# andEight_mouv4k.net
KiCad netlist of a schematic drawn in EAGLE
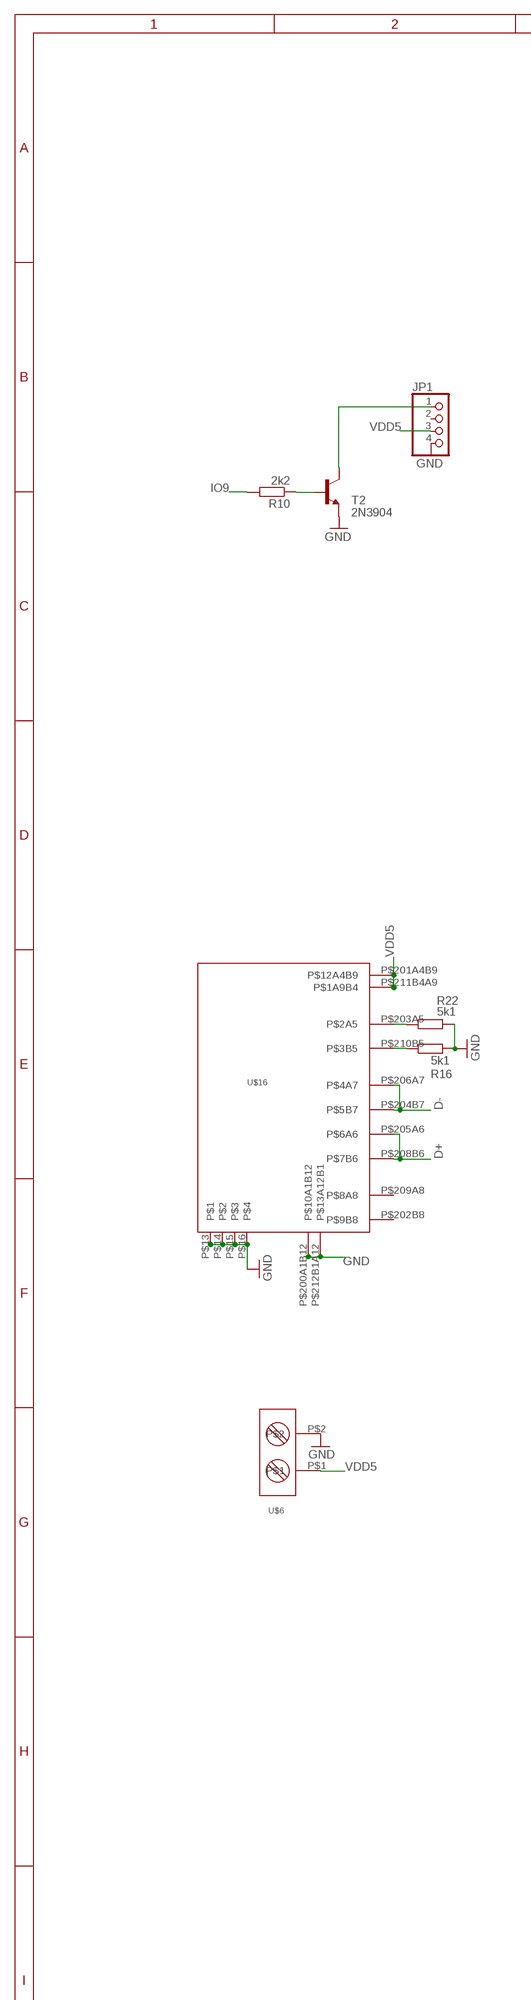
[diagram p0: schematic, sheet 1, part 1 of 2]
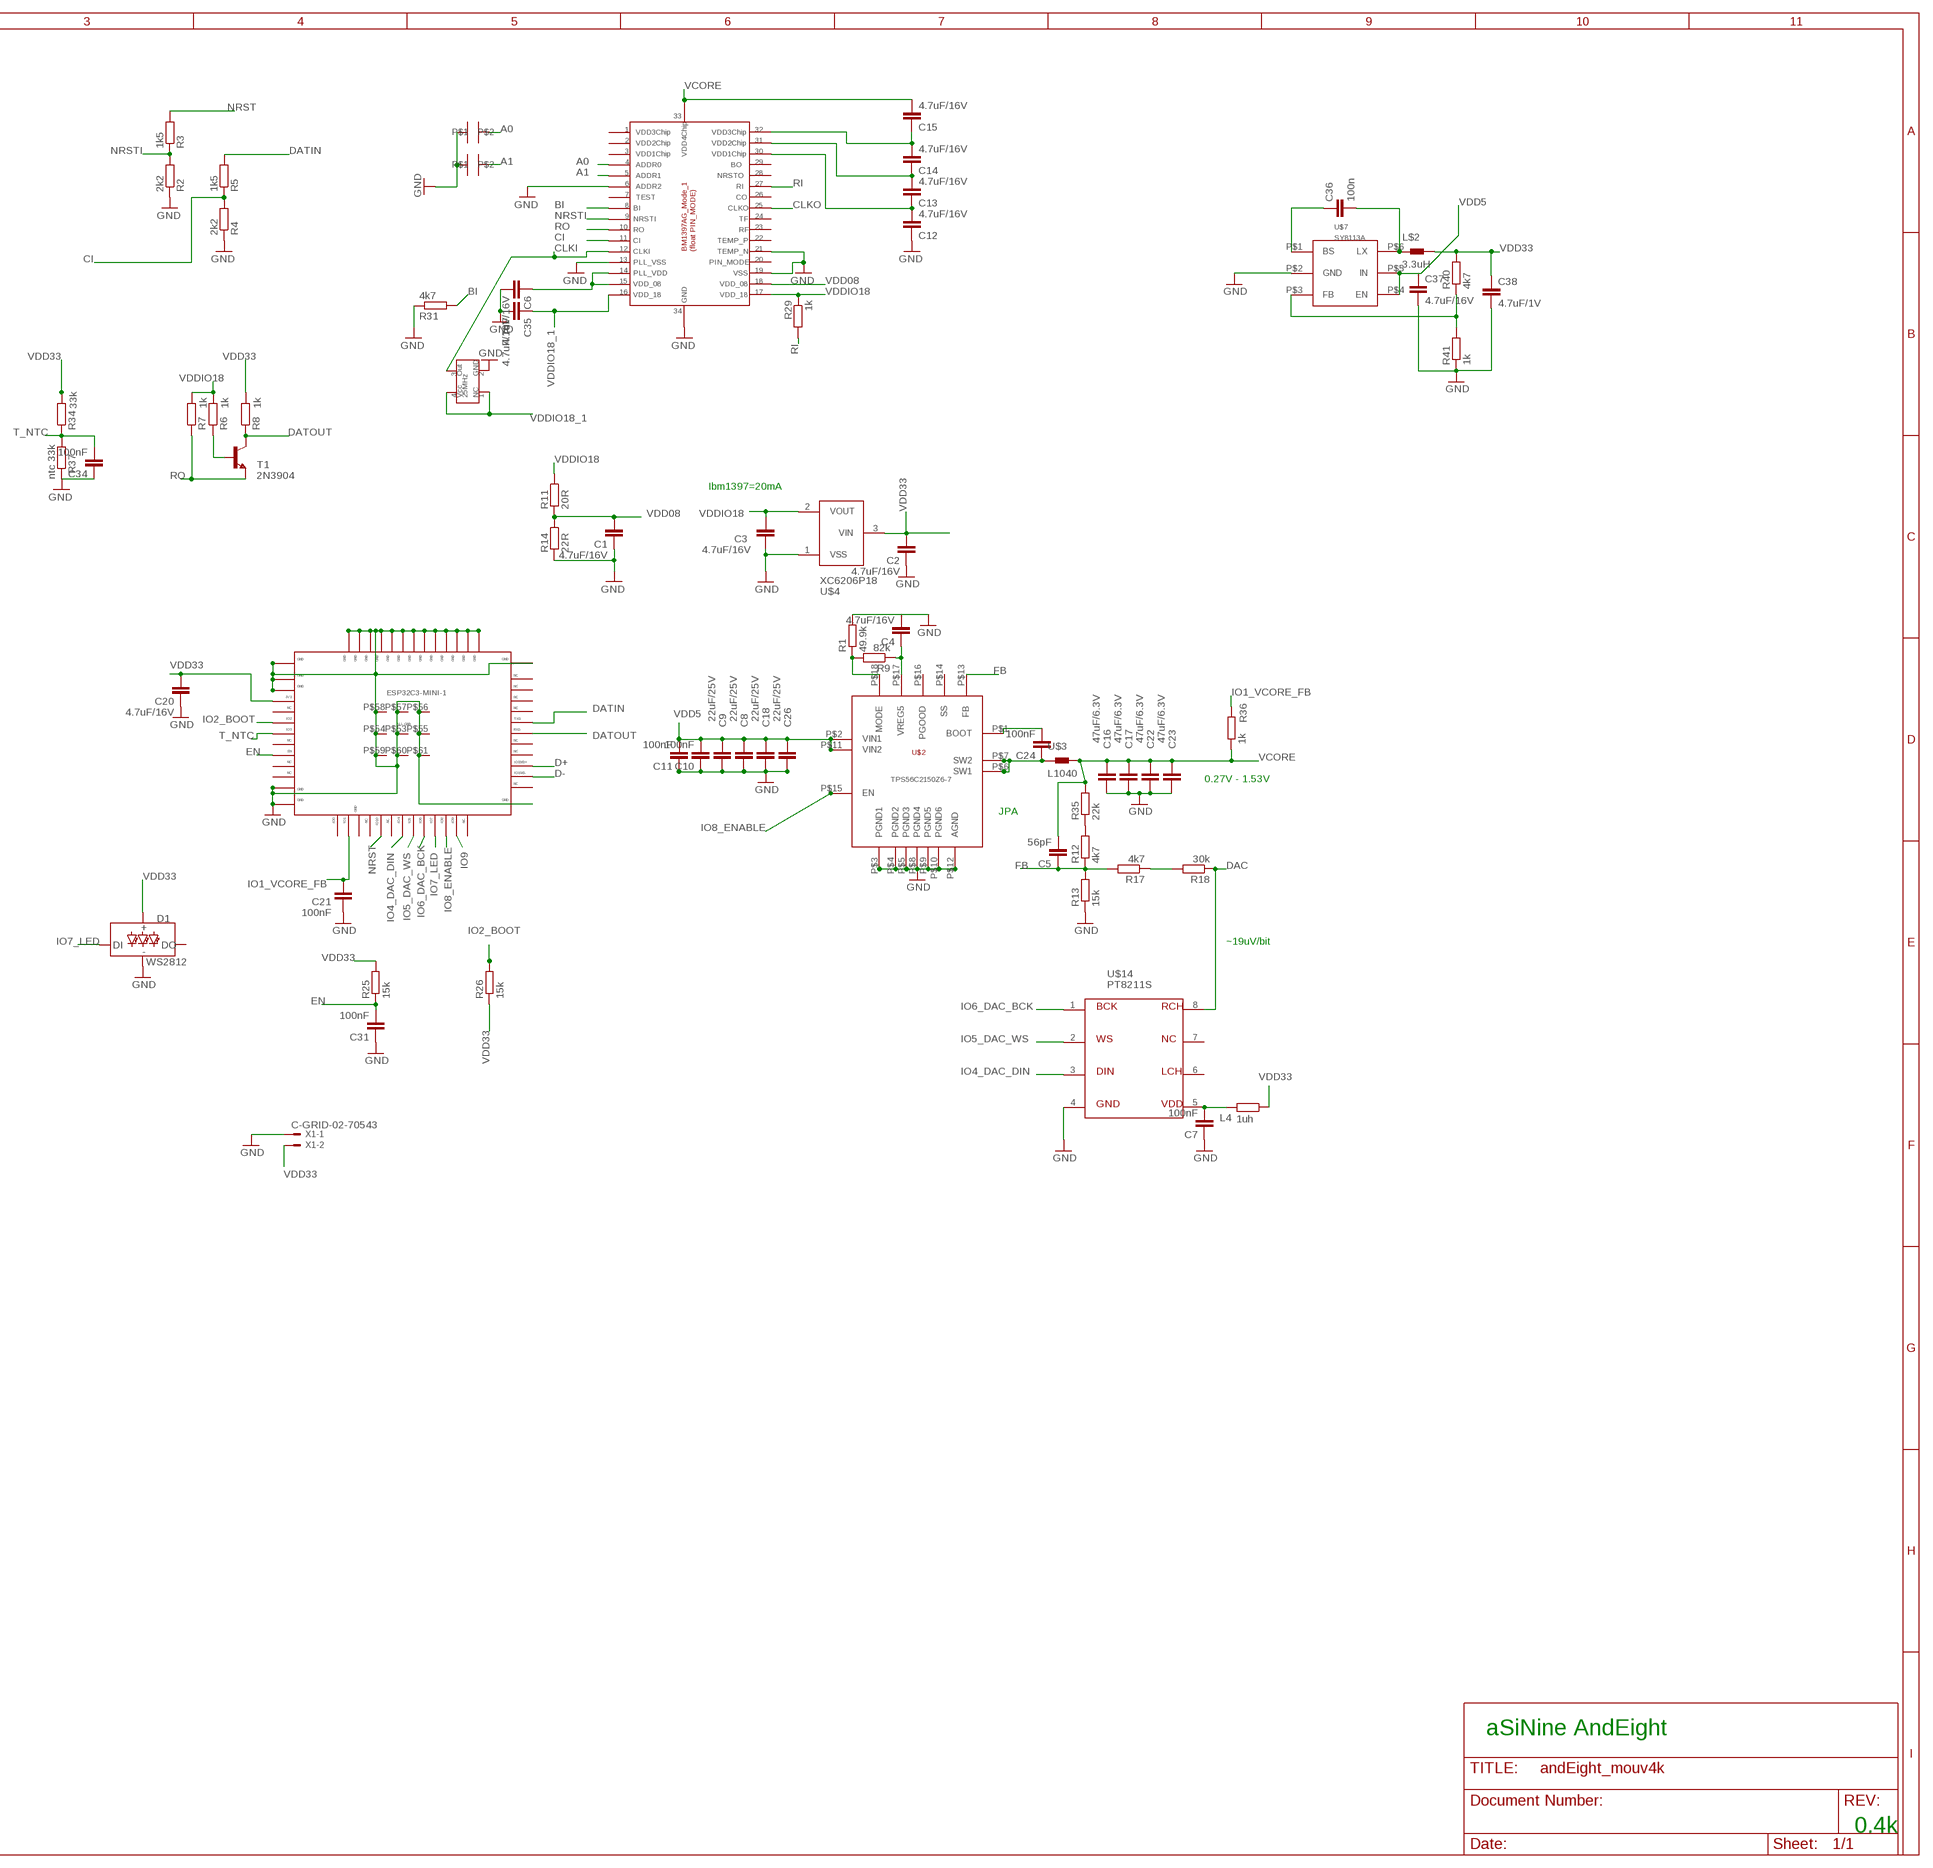
[diagram p1: schematic, sheet 1, part 2 of 2]

(export (version "E")
  (design (tool "Eeschema 10.0.6"))
  (components
    (comp (ref "A0")
      (value "SOLDERJUMPER")
      (footprint "eagle-import:SOLDERJUMPER")
      (libsource (lib "eagle-import") (part "SOLDERJUMPER"))
    )
    (comp (ref "A1")
      (value "SOLDERJUMPER")
      (footprint "eagle-import:SOLDERJUMPER")
      (libsource (lib "eagle-import") (part "SOLDERJUMPER"))
    )
    (comp (ref "C1")
      (value "4.7uF/16V")
      (footprint "eagle-import:C0402")
      (libsource (lib "eagle-import") (part "C-EUC0402"))
    )
    (comp (ref "C2")
      (value "4.7uF/16V")
      (footprint "eagle-import:C0402")
      (libsource (lib "eagle-import") (part "C-EUC0402"))
    )
    (comp (ref "C3")
      (value "4.7uF/16V")
      (footprint "eagle-import:C0402")
      (libsource (lib "eagle-import") (part "C-EUC0402"))
    )
    (comp (ref "C4")
      (value "4.7uF/16V")
      (footprint "eagle-import:C0402")
      (libsource (lib "eagle-import") (part "C-EUC0402"))
    )
    (comp (ref "C5")
      (value "56pF")
      (footprint "eagle-import:C0402")
      (libsource (lib "eagle-import") (part "C-EUC0402"))
    )
    (comp (ref "C6")
      (value "4.7uF/16V")
      (footprint "eagle-import:C0402")
      (libsource (lib "eagle-import") (part "C-EUC0402"))
    )
    (comp (ref "C7")
      (value "100nF")
      (footprint "eagle-import:C0402")
      (libsource (lib "eagle-import") (part "C-EUC0402"))
    )
    (comp (ref "C8")
      (value "22uF/25V")
      (footprint "eagle-import:C0805")
      (libsource (lib "eagle-import") (part "C-EUC0805"))
    )
    (comp (ref "C9")
      (value "22uF/25V")
      (footprint "eagle-import:C0805")
      (libsource (lib "eagle-import") (part "C-EUC0805"))
    )
    (comp (ref "C10")
      (value "100nF")
      (footprint "eagle-import:C0402")
      (libsource (lib "eagle-import") (part "C-EUC0402"))
    )
    (comp (ref "C11")
      (value "100nF")
      (footprint "eagle-import:C0402")
      (libsource (lib "eagle-import") (part "C-EUC0402"))
    )
    (comp (ref "C12")
      (value "4.7uF/16V")
      (footprint "eagle-import:C0402")
      (libsource (lib "eagle-import") (part "C-EUC0402"))
    )
    (comp (ref "C13")
      (value "4.7uF/16V")
      (footprint "eagle-import:C0402")
      (libsource (lib "eagle-import") (part "C-EUC0402"))
    )
    (comp (ref "C14")
      (value "4.7uF/16V")
      (footprint "eagle-import:C0402")
      (libsource (lib "eagle-import") (part "C-EUC0402"))
    )
    (comp (ref "C15")
      (value "4.7uF/16V")
      (footprint "eagle-import:C0402")
      (libsource (lib "eagle-import") (part "C-EUC0402"))
    )
    (comp (ref "C16")
      (value "47uF/6.3V")
      (footprint "eagle-import:C0805")
      (libsource (lib "eagle-import") (part "C-EUC0805"))
    )
    (comp (ref "C17")
      (value "47uF/6.3V")
      (footprint "eagle-import:C0805")
      (libsource (lib "eagle-import") (part "C-EUC0805"))
    )
    (comp (ref "C18")
      (value "22uF/25V")
      (footprint "eagle-import:C0805")
      (libsource (lib "eagle-import") (part "C-EUC0805"))
    )
    (comp (ref "C20")
      (value "4.7uF/16V")
      (footprint "eagle-import:C0603")
      (libsource (lib "eagle-import") (part "C-EUC0603"))
    )
    (comp (ref "C21")
      (value "100nF")
      (footprint "eagle-import:C0603")
      (libsource (lib "eagle-import") (part "C-EUC0603"))
    )
    (comp (ref "C22")
      (value "47uF/6.3V")
      (footprint "eagle-import:C0805")
      (libsource (lib "eagle-import") (part "C-EUC0805"))
    )
    (comp (ref "C23")
      (value "47uF/6.3V")
      (footprint "eagle-import:C0805")
      (libsource (lib "eagle-import") (part "C-EUC0805"))
    )
    (comp (ref "C24")
      (value "100nF")
      (footprint "eagle-import:C0402")
      (libsource (lib "eagle-import") (part "C-EUC0402"))
    )
    (comp (ref "C26")
      (value "22uF/25V")
      (footprint "eagle-import:C0805")
      (libsource (lib "eagle-import") (part "C-EUC0805"))
    )
    (comp (ref "C31")
      (value "100nF")
      (footprint "eagle-import:C0402")
      (libsource (lib "eagle-import") (part "C-EUC0402"))
    )
    (comp (ref "C34")
      (value "100nF")
      (footprint "eagle-import:C0402")
      (libsource (lib "eagle-import") (part "C-EUC0402"))
    )
    (comp (ref "C35")
      (value "4.7uF/16V")
      (footprint "eagle-import:C0402")
      (libsource (lib "eagle-import") (part "C-EUC0402"))
    )
    (comp (ref "C36")
      (value "100n")
      (footprint "eagle-import:C0402")
      (libsource (lib "eagle-import") (part "C-EUC0402"))
    )
    (comp (ref "C37")
      (value "4.7uF/16V")
      (footprint "eagle-import:C0402")
      (libsource (lib "eagle-import") (part "C-EUC0402"))
    )
    (comp (ref "C38")
      (value "4.7uF/1V")
      (footprint "eagle-import:C0402")
      (libsource (lib "eagle-import") (part "C-EUC0402"))
    )
    (comp (ref "D1")
      (value "WS2812")
      (footprint "eagle-import:WS2812-5X5-4PIN")
      (libsource (lib "eagle-import") (part "WS2812_5050"))
    )
    (comp (ref "ESP32C3-MINI-1")
      (value "ESP32-C3-MINI-1")
      (footprint "eagle-import:ESP32C3MINI")
      (libsource (lib "eagle-import") (part "ESP32C3MINI"))
    )
    (comp (ref "JP1")
      (value "PINHD-1X4/90")
      (footprint "eagle-import:1X04_90")
      (libsource (lib "eagle-import") (part "PINHD-1X4/90"))
    )
    (comp (ref "L$2")
      (value "3.3uH")
      (footprint "eagle-import:NR201610")
      (libsource (lib "eagle-import") (part "NR201610"))
    )
    (comp (ref "L4")
      (value "1uh")
      (footprint "eagle-import:R0402")
      (libsource (lib "eagle-import") (part "R-EU_R0402"))
    )
    (comp (ref "R1")
      (value "49.9k")
      (footprint "eagle-import:R0402")
      (libsource (lib "eagle-import") (part "R-EU_R0402"))
    )
    (comp (ref "R2")
      (value "2k2")
      (footprint "eagle-import:R0402")
      (libsource (lib "eagle-import") (part "R-EU_R0402"))
    )
    (comp (ref "R3")
      (value "1k5")
      (footprint "eagle-import:R0402")
      (libsource (lib "eagle-import") (part "R-EU_R0402"))
    )
    (comp (ref "R4")
      (value "2k2")
      (footprint "eagle-import:R0402")
      (libsource (lib "eagle-import") (part "R-EU_R0402"))
    )
    (comp (ref "R5")
      (value "1k5")
      (footprint "eagle-import:R0402")
      (libsource (lib "eagle-import") (part "R-EU_R0402"))
    )
    (comp (ref "R6")
      (value "1k")
      (footprint "eagle-import:R0402")
      (libsource (lib "eagle-import") (part "R-EU_R0402"))
    )
    (comp (ref "R7")
      (value "1k")
      (footprint "eagle-import:R0402")
      (libsource (lib "eagle-import") (part "R-EU_R0402"))
    )
    (comp (ref "R8")
      (value "1k")
      (footprint "eagle-import:R0402")
      (libsource (lib "eagle-import") (part "R-EU_R0402"))
    )
    (comp (ref "R9")
      (value "82k")
      (footprint "eagle-import:R0402")
      (libsource (lib "eagle-import") (part "R-EU_R0402"))
    )
    (comp (ref "R10")
      (value "2k2")
      (footprint "eagle-import:R0402")
      (libsource (lib "eagle-import") (part "R-EU_R0402"))
    )
    (comp (ref "R11")
      (value "20R")
      (footprint "eagle-import:R0402")
      (libsource (lib "eagle-import") (part "R-EU_R0402"))
    )
    (comp (ref "R12")
      (value "4k7")
      (footprint "eagle-import:R0402")
      (libsource (lib "eagle-import") (part "R-EU_R0402"))
    )
    (comp (ref "R13")
      (value "15k")
      (footprint "eagle-import:R0402")
      (libsource (lib "eagle-import") (part "R-EU_R0402"))
    )
    (comp (ref "R14")
      (value "22R")
      (footprint "eagle-import:R0402")
      (libsource (lib "eagle-import") (part "R-EU_R0402"))
    )
    (comp (ref "R16")
      (value "5k1")
      (footprint "eagle-import:R0402")
      (libsource (lib "eagle-import") (part "R-EU_R0402"))
    )
    (comp (ref "R17")
      (value "4k7")
      (footprint "eagle-import:R0402")
      (libsource (lib "eagle-import") (part "R-EU_R0402"))
    )
    (comp (ref "R18")
      (value "30k")
      (footprint "eagle-import:R0402")
      (libsource (lib "eagle-import") (part "R-EU_R0402"))
    )
    (comp (ref "R22")
      (value "5k1")
      (footprint "eagle-import:R0402")
      (libsource (lib "eagle-import") (part "R-EU_R0402"))
    )
    (comp (ref "R25")
      (value "15k")
      (footprint "eagle-import:R0402")
      (libsource (lib "eagle-import") (part "R-EU_R0402"))
    )
    (comp (ref "R26")
      (value "15k")
      (footprint "eagle-import:R0402")
      (libsource (lib "eagle-import") (part "R-EU_R0402"))
    )
    (comp (ref "R29")
      (value "1k")
      (footprint "eagle-import:R0402")
      (libsource (lib "eagle-import") (part "R-EU_R0402"))
    )
    (comp (ref "R31")
      (value "4k7")
      (footprint "eagle-import:R0402")
      (libsource (lib "eagle-import") (part "R-EU_R0402"))
    )
    (comp (ref "R34")
      (value "33k")
      (footprint "eagle-import:R0603")
      (libsource (lib "eagle-import") (part "R-EU_R0603"))
    )
    (comp (ref "R35")
      (value "22k")
      (footprint "eagle-import:R0402")
      (libsource (lib "eagle-import") (part "R-EU_R0402"))
    )
    (comp (ref "R36")
      (value "1k")
      (footprint "eagle-import:R0402")
      (libsource (lib "eagle-import") (part "R-EU_R0402"))
    )
    (comp (ref "R37")
      (value "ntc 33k")
      (footprint "eagle-import:R0402")
      (libsource (lib "eagle-import") (part "R-EU_R0402"))
    )
    (comp (ref "R40")
      (value "4k7")
      (footprint "eagle-import:R0402")
      (libsource (lib "eagle-import") (part "R-EU_R0402"))
    )
    (comp (ref "R41")
      (value "1k")
      (footprint "eagle-import:R0402")
      (libsource (lib "eagle-import") (part "R-EU_R0402"))
    )
    (comp (ref "T1")
      (value "2N3904")
      (footprint "eagle-import:SOT23")
      (libsource (lib "eagle-import") (part "BC847"))
    )
    (comp (ref "T2")
      (value "2N3904")
      (footprint "eagle-import:SOT23")
      (libsource (lib "eagle-import") (part "BC847"))
    )
    (comp (ref "U$1")
      (value "BM1397-1")
      (footprint "eagle-import:BM1391")
      (libsource (lib "eagle-import") (part "BM1397-1"))
    )
    (comp (ref "U$2")
      (value "TPS56C2150Z6-7")
      (footprint "eagle-import:VQFN-HR")
      (libsource (lib "eagle-import") (part "TPS56C2150Z6-7"))
    )
    (comp (ref "U$3")
      (value "L1040")
      (footprint "eagle-import:L1040")
      (libsource (lib "eagle-import") (part "L1040"))
    )
    (comp (ref "U$4")
      (value "XC6206P18")
      (footprint "eagle-import:SOT23")
      (libsource (lib "eagle-import") (part "XC6206P"))
    )
    (comp (ref "U$6")
      (value "DG301-50")
      (footprint "eagle-import:DG301-50")
      (libsource (lib "eagle-import") (part "DG301-50"))
    )
    (comp (ref "U$7")
      (value "SY8113A")
      (footprint "eagle-import:SOT23L-6")
      (libsource (lib "eagle-import") (part "SY8113A"))
    )
    (comp (ref "U$14")
      (value "PT8211S")
      (footprint "eagle-import:SO-8")
      (libsource (lib "eagle-import") (part "PT8211"))
    )
    (comp (ref "U$16")
      (value "USBCTHT")
      (footprint "eagle-import:USBCSMTTHT")
      (libsource (lib "eagle-import") (part "USBCTHT"))
    )
    (comp (ref "U$22")
      (value "25MHz")
      (footprint "eagle-import:3225")
      (libsource (lib "eagle-import") (part "OSC3225"))
    )
    (comp (ref "X1")
      (value "C-GRID-02-70543")
      (footprint "eagle-import:70543-02")
      (libsource (lib "eagle-import") (part "C-GRID-02-70543"))
    )
  )
  (nets
    (net (code "1") (name "/A0") (class "Default")
      (node (ref "A0") (pin "P$1") (pinfunction "P$1_P$1") (pintype "bidirectional"))
      (node (ref "U$1") (pin "P$4") (pinfunction "P$4_P$4") (pintype "bidirectional"))
    )
    (net (code "2") (name "/A1") (class "Default")
      (node (ref "A1") (pin "P$1") (pinfunction "P$1_P$1") (pintype "bidirectional"))
      (node (ref "U$1") (pin "P$5") (pinfunction "P$5_P$5") (pintype "bidirectional"))
    )
    (net (code "3") (name "/BI") (class "Default")
      (node (ref "R31") (pin "2") (pinfunction "2_2") (pintype "passive"))
      (node (ref "U$1") (pin "P$8") (pinfunction "P$8_P$8") (pintype "bidirectional"))
    )
    (net (code "4") (name "/CI") (class "Default")
      (node (ref "R4") (pin "2") (pinfunction "2_2") (pintype "passive"))
      (node (ref "R5") (pin "1") (pinfunction "1_1") (pintype "passive"))
      (node (ref "U$1") (pin "P$11") (pinfunction "P$11_P$11") (pintype "bidirectional"))
    )
    (net (code "5") (name "/CLKI") (class "Default")
      (node (ref "U$1") (pin "P$12") (pinfunction "P$12_P$12") (pintype "bidirectional"))
      (node (ref "U$22") (pin "P$3") (pinfunction "P$3_P$3") (pintype "bidirectional"))
    )
    (net (code "6") (name "/CLKO") (class "Default")
      (node (ref "U$1") (pin "P$25") (pinfunction "P$25_P$25") (pintype "bidirectional"))
    )
    (net (code "7") (name "/D+") (class "Default")
      (node (ref "ESP32C3-MINI-1") (pin "P$27") (pinfunction "P$27_P$27") (pintype "bidirectional"))
      (node (ref "U$16") (pin "P$205A6") (pinfunction "P$6A6_P$205A6") (pintype "bidirectional"))
      (node (ref "U$16") (pin "P$208B6") (pinfunction "P$7B6_P$208B6") (pintype "bidirectional"))
    )
    (net (code "8") (name "/D-") (class "Default")
      (node (ref "ESP32C3-MINI-1") (pin "P$26") (pinfunction "P$26_P$26") (pintype "bidirectional"))
      (node (ref "U$16") (pin "P$204B7") (pinfunction "P$5B7_P$204B7") (pintype "bidirectional"))
      (node (ref "U$16") (pin "P$206A7") (pinfunction "P$4A7_P$206A7") (pintype "bidirectional"))
    )
    (net (code "9") (name "/DAC") (class "Default")
      (node (ref "R18") (pin "1") (pinfunction "1_1") (pintype "passive"))
      (node (ref "U$14") (pin "8") (pinfunction "P$8_8") (pintype "bidirectional"))
    )
    (net (code "10") (name "/DATIN") (class "Default")
      (node (ref "ESP32C3-MINI-1") (pin "P$31") (pinfunction "P$31_P$31") (pintype "bidirectional"))
      (node (ref "R5") (pin "2") (pinfunction "2_2") (pintype "passive"))
    )
    (net (code "11") (name "/DATOUT") (class "Default")
      (node (ref "ESP32C3-MINI-1") (pin "P$30") (pinfunction "P$30_P$30") (pintype "bidirectional"))
      (node (ref "R8") (pin "1") (pinfunction "1_1") (pintype "passive"))
      (node (ref "T1") (pin "3") (pinfunction "C_3") (pintype "passive"))
    )
    (net (code "12") (name "/EN") (class "Default")
      (node (ref "C31") (pin "2") (pinfunction "2_2") (pintype "passive"))
      (node (ref "ESP32C3-MINI-1") (pin "P$8") (pinfunction "P$8_P$8") (pintype "bidirectional"))
      (node (ref "R25") (pin "1") (pinfunction "1_1") (pintype "passive"))
    )
    (net (code "13") (name "/FB") (class "Default")
      (node (ref "C5") (pin "1") (pinfunction "1_1") (pintype "passive"))
      (node (ref "R12") (pin "1") (pinfunction "1_1") (pintype "passive"))
      (node (ref "R13") (pin "2") (pinfunction "2_2") (pintype "passive"))
      (node (ref "R17") (pin "2") (pinfunction "2_2") (pintype "passive"))
      (node (ref "U$2") (pin "P$13") (pinfunction "FB_P$13") (pintype "bidirectional"))
    )
    (net (code "14") (name "/IO1_VCORE_FB") (class "Default")
      (node (ref "C21") (pin "2") (pinfunction "2_2") (pintype "passive"))
      (node (ref "ESP32C3-MINI-1") (pin "P$13") (pinfunction "P$13_P$13") (pintype "bidirectional"))
      (node (ref "R36") (pin "2") (pinfunction "2_2") (pintype "passive"))
    )
    (net (code "15") (name "/IO2_BOOT") (class "Default")
      (node (ref "ESP32C3-MINI-1") (pin "P$5") (pinfunction "P$5_P$5") (pintype "bidirectional"))
      (node (ref "R26") (pin "2") (pinfunction "2_2") (pintype "passive"))
    )
    (net (code "16") (name "/IO4_DAC_DIN") (class "Default")
      (node (ref "ESP32C3-MINI-1") (pin "P$18") (pinfunction "P$18_P$18") (pintype "bidirectional"))
      (node (ref "U$14") (pin "3") (pinfunction "P$3_3") (pintype "bidirectional"))
    )
    (net (code "17") (name "/IO5_DAC_WS") (class "Default")
      (node (ref "ESP32C3-MINI-1") (pin "P$19") (pinfunction "P$19_P$19") (pintype "bidirectional"))
      (node (ref "U$14") (pin "2") (pinfunction "P$2_2") (pintype "bidirectional"))
    )
    (net (code "18") (name "/IO6_DAC_BCK") (class "Default")
      (node (ref "ESP32C3-MINI-1") (pin "P$20") (pinfunction "P$20_P$20") (pintype "bidirectional"))
      (node (ref "U$14") (pin "1") (pinfunction "P$1_1") (pintype "bidirectional"))
    )
    (net (code "19") (name "/IO7_LED") (class "Default")
      (node (ref "D1") (pin "DI") (pinfunction "DI_DI") (pintype "bidirectional"))
      (node (ref "ESP32C3-MINI-1") (pin "P$21") (pinfunction "P$21_P$21") (pintype "bidirectional"))
    )
    (net (code "20") (name "/IO8_ENABLE") (class "Default")
      (node (ref "ESP32C3-MINI-1") (pin "P$22") (pinfunction "P$22_P$22") (pintype "bidirectional"))
      (node (ref "U$2") (pin "P$15") (pinfunction "EN_P$15") (pintype "bidirectional"))
    )
    (net (code "21") (name "/IO9") (class "Default")
      (node (ref "ESP32C3-MINI-1") (pin "P$23") (pinfunction "P$23_P$23") (pintype "bidirectional"))
      (node (ref "R10") (pin "2") (pinfunction "2_2") (pintype "passive"))
    )
    (net (code "22") (name "/NRST") (class "Default")
      (node (ref "ESP32C3-MINI-1") (pin "P$16") (pinfunction "P$16_P$16") (pintype "bidirectional"))
      (node (ref "R3") (pin "2") (pinfunction "2_2") (pintype "passive"))
    )
    (net (code "23") (name "/NRSTI") (class "Default")
      (node (ref "R2") (pin "2") (pinfunction "2_2") (pintype "passive"))
      (node (ref "R3") (pin "1") (pinfunction "1_1") (pintype "passive"))
      (node (ref "U$1") (pin "P$9") (pinfunction "P$9_P$9") (pintype "bidirectional"))
    )
    (net (code "24") (name "/RI") (class "Default")
      (node (ref "R29") (pin "2") (pinfunction "2_2") (pintype "passive"))
      (node (ref "U$1") (pin "P$27") (pinfunction "P$27_P$27") (pintype "bidirectional"))
    )
    (net (code "25") (name "/RO") (class "Default")
      (node (ref "R7") (pin "1") (pinfunction "1_1") (pintype "passive"))
      (node (ref "T1") (pin "2") (pinfunction "E_2") (pintype "passive"))
      (node (ref "U$1") (pin "P$10") (pinfunction "P$10_P$10") (pintype "bidirectional"))
    )
    (net (code "26") (name "/T_NTC") (class "Default")
      (node (ref "C34") (pin "2") (pinfunction "2_2") (pintype "passive"))
      (node (ref "ESP32C3-MINI-1") (pin "P$6") (pinfunction "P$6_P$6") (pintype "bidirectional"))
      (node (ref "R34") (pin "1") (pinfunction "1_1") (pintype "passive"))
      (node (ref "R37") (pin "2") (pinfunction "2_2") (pintype "passive"))
    )
    (net (code "27") (name "/VCORE") (class "Default")
      (node (ref "C15") (pin "2") (pinfunction "2_2") (pintype "passive"))
      (node (ref "C16") (pin "1") (pinfunction "1_1") (pintype "passive"))
      (node (ref "C17") (pin "1") (pinfunction "1_1") (pintype "passive"))
      (node (ref "C22") (pin "1") (pinfunction "1_1") (pintype "passive"))
      (node (ref "C23") (pin "1") (pinfunction "1_1") (pintype "passive"))
      (node (ref "C5") (pin "2") (pinfunction "2_2") (pintype "passive"))
      (node (ref "R35") (pin "2") (pinfunction "2_2") (pintype "passive"))
      (node (ref "R36") (pin "1") (pinfunction "1_1") (pintype "passive"))
      (node (ref "U$1") (pin "P$33") (pinfunction "P$33_P$33") (pintype "bidirectional"))
      (node (ref "U$3") (pin "P$2") (pinfunction "2_P$2") (pintype "passive"))
    )
    (net (code "28") (name "/VDD5") (class "Default")
      (node (ref "C10") (pin "2") (pinfunction "2_2") (pintype "passive"))
      (node (ref "C11") (pin "2") (pinfunction "2_2") (pintype "passive"))
      (node (ref "C18") (pin "1") (pinfunction "1_1") (pintype "passive"))
      (node (ref "C26") (pin "1") (pinfunction "1_1") (pintype "passive"))
      (node (ref "C37") (pin "1") (pinfunction "1_1") (pintype "passive"))
      (node (ref "C8") (pin "1") (pinfunction "1_1") (pintype "passive"))
      (node (ref "C9") (pin "1") (pinfunction "1_1") (pintype "passive"))
      (node (ref "JP1") (pin "3") (pinfunction "3_3") (pintype "passive"))
      (node (ref "U$16") (pin "P$201A4B9") (pinfunction "P$12A4B9_P$201A4B9") (pintype "bidirectional"))
      (node (ref "U$16") (pin "P$211B4A9") (pinfunction "P$1A9B4_P$211B4A9") (pintype "bidirectional"))
      (node (ref "U$2") (pin "P$11") (pinfunction "VIN2_P$11") (pintype "bidirectional"))
      (node (ref "U$2") (pin "P$2") (pinfunction "VIN1_P$2") (pintype "bidirectional"))
      (node (ref "U$6") (pin "P$1") (pinfunction "P$1_P$1") (pintype "bidirectional"))
      (node (ref "U$7") (pin "P$4") (pinfunction "EN_P$4") (pintype "bidirectional"))
      (node (ref "U$7") (pin "P$5") (pinfunction "IN_P$5") (pintype "bidirectional"))
    )
    (net (code "29") (name "/VDD08") (class "Default")
      (node (ref "C1") (pin "2") (pinfunction "2_2") (pintype "passive"))
      (node (ref "R11") (pin "2") (pinfunction "2_2") (pintype "passive"))
      (node (ref "R14") (pin "1") (pinfunction "1_1") (pintype "passive"))
      (node (ref "U$1") (pin "P$18") (pinfunction "P$18_P$18") (pintype "bidirectional"))
    )
    (net (code "30") (name "/VDD33") (class "Default")
      (node (ref "C2") (pin "2") (pinfunction "2_2") (pintype "passive"))
      (node (ref "C20") (pin "2") (pinfunction "2_2") (pintype "passive"))
      (node (ref "C38") (pin "1") (pinfunction "1_1") (pintype "passive"))
      (node (ref "D1") (pin "VCC") (pinfunction "VCC_VCC") (pintype "bidirectional"))
      (node (ref "ESP32C3-MINI-1") (pin "P$3") (pinfunction "P$3_P$3") (pintype "bidirectional"))
      (node (ref "L$2") (pin "P$2") (pinfunction "2_P$2") (pintype "passive"))
      (node (ref "L4") (pin "1") (pinfunction "1_1") (pintype "passive"))
      (node (ref "R25") (pin "2") (pinfunction "2_2") (pintype "passive"))
      (node (ref "R26") (pin "1") (pinfunction "1_1") (pintype "passive"))
      (node (ref "R34") (pin "2") (pinfunction "2_2") (pintype "passive"))
      (node (ref "R40") (pin "2") (pinfunction "2_2") (pintype "passive"))
      (node (ref "R8") (pin "2") (pinfunction "2_2") (pintype "passive"))
      (node (ref "U$4") (pin "3") (pinfunction "VIN_3") (pintype "bidirectional"))
      (node (ref "X1") (pin "2") (pinfunction "S_2") (pintype "passive"))
    )
    (net (code "31") (name "/VDDIO18") (class "Default")
      (node (ref "C3") (pin "2") (pinfunction "2_2") (pintype "passive"))
      (node (ref "R11") (pin "1") (pinfunction "1_1") (pintype "passive"))
      (node (ref "R29") (pin "1") (pinfunction "1_1") (pintype "passive"))
      (node (ref "R6") (pin "2") (pinfunction "2_2") (pintype "passive"))
      (node (ref "R7") (pin "2") (pinfunction "2_2") (pintype "passive"))
      (node (ref "U$1") (pin "P$17") (pinfunction "P$17_P$17") (pintype "bidirectional"))
      (node (ref "U$4") (pin "2") (pinfunction "VOUT_2") (pintype "bidirectional"))
    )
    (net (code "32") (name "/VDDIO18_1") (class "Default")
      (node (ref "C35") (pin "1") (pinfunction "1_1") (pintype "passive"))
      (node (ref "U$1") (pin "P$16") (pinfunction "P$16_P$16") (pintype "bidirectional"))
      (node (ref "U$22") (pin "P$1") (pinfunction "P$1_P$1") (pintype "bidirectional"))
      (node (ref "U$22") (pin "P$4") (pinfunction "P$4_P$4") (pintype "bidirectional"))
    )
    (net (code "33") (name "GND") (class "Default")
      (node (ref "A0") (pin "P$2") (pinfunction "P$2_P$2") (pintype "bidirectional"))
      (node (ref "A1") (pin "P$2") (pinfunction "P$2_P$2") (pintype "bidirectional"))
      (node (ref "C1") (pin "1") (pinfunction "1_1") (pintype "passive"))
      (node (ref "C10") (pin "1") (pinfunction "1_1") (pintype "passive"))
      (node (ref "C11") (pin "1") (pinfunction "1_1") (pintype "passive"))
      (node (ref "C12") (pin "1") (pinfunction "1_1") (pintype "passive"))
      (node (ref "C16") (pin "2") (pinfunction "2_2") (pintype "passive"))
      (node (ref "C17") (pin "2") (pinfunction "2_2") (pintype "passive"))
      (node (ref "C18") (pin "2") (pinfunction "2_2") (pintype "passive"))
      (node (ref "C2") (pin "1") (pinfunction "1_1") (pintype "passive"))
      (node (ref "C20") (pin "1") (pinfunction "1_1") (pintype "passive"))
      (node (ref "C21") (pin "1") (pinfunction "1_1") (pintype "passive"))
      (node (ref "C22") (pin "2") (pinfunction "2_2") (pintype "passive"))
      (node (ref "C23") (pin "2") (pinfunction "2_2") (pintype "passive"))
      (node (ref "C26") (pin "2") (pinfunction "2_2") (pintype "passive"))
      (node (ref "C3") (pin "1") (pinfunction "1_1") (pintype "passive"))
      (node (ref "C31") (pin "1") (pinfunction "1_1") (pintype "passive"))
      (node (ref "C34") (pin "1") (pinfunction "1_1") (pintype "passive"))
      (node (ref "C35") (pin "2") (pinfunction "2_2") (pintype "passive"))
      (node (ref "C37") (pin "2") (pinfunction "2_2") (pintype "passive"))
      (node (ref "C38") (pin "2") (pinfunction "2_2") (pintype "passive"))
      (node (ref "C4") (pin "2") (pinfunction "2_2") (pintype "passive"))
      (node (ref "C6") (pin "2") (pinfunction "2_2") (pintype "passive"))
      (node (ref "C7") (pin "1") (pinfunction "1_1") (pintype "passive"))
      (node (ref "C8") (pin "2") (pinfunction "2_2") (pintype "passive"))
      (node (ref "C9") (pin "2") (pinfunction "2_2") (pintype "passive"))
      (node (ref "D1") (pin "GND") (pinfunction "GND_GND") (pintype "bidirectional"))
      (node (ref "ESP32C3-MINI-1") (pin "P$1") (pinfunction "P$1_P$1") (pintype "bidirectional"))
      (node (ref "ESP32C3-MINI-1") (pin "P$11") (pinfunction "P$11_P$11") (pintype "bidirectional"))
      (node (ref "ESP32C3-MINI-1") (pin "P$2") (pinfunction "P$2_P$2") (pintype "bidirectional"))
      (node (ref "ESP32C3-MINI-1") (pin "P$36") (pinfunction "P$36_P$36") (pintype "bidirectional"))
      (node (ref "ESP32C3-MINI-1") (pin "P$37") (pinfunction "P$37_P$37") (pintype "bidirectional"))
      (node (ref "ESP32C3-MINI-1") (pin "P$38") (pinfunction "P$38_P$38") (pintype "bidirectional"))
      (node (ref "ESP32C3-MINI-1") (pin "P$39") (pinfunction "P$39_P$39") (pintype "bidirectional"))
      (node (ref "ESP32C3-MINI-1") (pin "P$40") (pinfunction "P$40_P$40") (pintype "bidirectional"))
      (node (ref "ESP32C3-MINI-1") (pin "P$41") (pinfunction "P$41_P$41") (pintype "bidirectional"))
      (node (ref "ESP32C3-MINI-1") (pin "P$42") (pinfunction "P$42_P$42") (pintype "bidirectional"))
      (node (ref "ESP32C3-MINI-1") (pin "P$43") (pinfunction "P$43_P$43") (pintype "bidirectional"))
      (node (ref "ESP32C3-MINI-1") (pin "P$44") (pinfunction "P$44_P$44") (pintype "bidirectional"))
      (node (ref "ESP32C3-MINI-1") (pin "P$45") (pinfunction "P$45_P$45") (pintype "bidirectional"))
      (node (ref "ESP32C3-MINI-1") (pin "P$46") (pinfunction "P$46_P$46") (pintype "bidirectional"))
      (node (ref "ESP32C3-MINI-1") (pin "P$47") (pinfunction "P$47_P$47") (pintype "bidirectional"))
      (node (ref "ESP32C3-MINI-1") (pin "P$48") (pinfunction "P$48_P$48") (pintype "bidirectional"))
      (node (ref "ESP32C3-MINI-1") (pin "P$49") (pinfunction "P$50_P$49") (pintype "bidirectional"))
      (node (ref "ESP32C3-MINI-1") (pin "P$50") (pinfunction "P$51_P$50") (pintype "bidirectional"))
      (node (ref "ESP32C3-MINI-1") (pin "P$51") (pinfunction "P$52_P$51") (pintype "bidirectional"))
      (node (ref "ESP32C3-MINI-1") (pin "P$52") (pinfunction "P$53_P$52") (pintype "bidirectional"))
      (node (ref "ESP32C3-MINI-1") (pin "P$53") (pinfunction "P$54_P$53") (pintype "bidirectional"))
      (node (ref "ESP32C3-MINI-1") (pin "P$54") (pinfunction "P$55_P$54") (pintype "bidirectional"))
      (node (ref "ESP32C3-MINI-1") (pin "P$55") (pinfunction "P$56_P$55") (pintype "bidirectional"))
      (node (ref "ESP32C3-MINI-1") (pin "P$56") (pinfunction "P$57_P$56") (pintype "bidirectional"))
      (node (ref "ESP32C3-MINI-1") (pin "P$57") (pinfunction "P$58_P$57") (pintype "bidirectional"))
      (node (ref "ESP32C3-MINI-1") (pin "P$58") (pinfunction "P$59_P$58") (pintype "bidirectional"))
      (node (ref "ESP32C3-MINI-1") (pin "P$59") (pinfunction "P$60_P$59") (pintype "bidirectional"))
      (node (ref "ESP32C3-MINI-1") (pin "P$60") (pinfunction "P$61_P$60") (pintype "bidirectional"))
      (node (ref "ESP32C3-MINI-1") (pin "P$61") (pinfunction "P$62_P$61") (pintype "bidirectional"))
      (node (ref "JP1") (pin "4") (pinfunction "4_4") (pintype "passive"))
      (node (ref "R1") (pin "2") (pinfunction "2_2") (pintype "passive"))
      (node (ref "R13") (pin "1") (pinfunction "1_1") (pintype "passive"))
      (node (ref "R14") (pin "2") (pinfunction "2_2") (pintype "passive"))
      (node (ref "R16") (pin "2") (pinfunction "2_2") (pintype "passive"))
      (node (ref "R2") (pin "1") (pinfunction "1_1") (pintype "passive"))
      (node (ref "R22") (pin "2") (pinfunction "2_2") (pintype "passive"))
      (node (ref "R31") (pin "1") (pinfunction "1_1") (pintype "passive"))
      (node (ref "R37") (pin "1") (pinfunction "1_1") (pintype "passive"))
      (node (ref "R4") (pin "1") (pinfunction "1_1") (pintype "passive"))
      (node (ref "R41") (pin "1") (pinfunction "1_1") (pintype "passive"))
      (node (ref "T2") (pin "2") (pinfunction "E_2") (pintype "passive"))
      (node (ref "U$1") (pin "P$13") (pinfunction "P$13_P$13") (pintype "bidirectional"))
      (node (ref "U$1") (pin "P$19") (pinfunction "P$19_P$19") (pintype "bidirectional"))
      (node (ref "U$1") (pin "P$21") (pinfunction "P$21_P$21") (pintype "bidirectional"))
      (node (ref "U$1") (pin "P$34") (pinfunction "P$34_P$34") (pintype "bidirectional"))
      (node (ref "U$1") (pin "P$6") (pinfunction "P$6_P$6") (pintype "bidirectional"))
      (node (ref "U$14") (pin "4") (pinfunction "P$4_4") (pintype "power_in"))
      (node (ref "U$16") (pin "P$13") (pinfunction "P$1_P$13") (pintype "bidirectional"))
      (node (ref "U$16") (pin "P$14") (pinfunction "P$2_P$14") (pintype "bidirectional"))
      (node (ref "U$16") (pin "P$15") (pinfunction "P$3_P$15") (pintype "bidirectional"))
      (node (ref "U$16") (pin "P$16") (pinfunction "P$4_P$16") (pintype "bidirectional"))
      (node (ref "U$16") (pin "P$200A1B12") (pinfunction "P$10A1B12_P$200A1B12") (pintype "bidirectional"))
      (node (ref "U$16") (pin "P$212B1A12") (pinfunction "P$13A12B1_P$212B1A12") (pintype "bidirectional"))
      (node (ref "U$2") (pin "P$10") (pinfunction "PGND6_P$10") (pintype "bidirectional"))
      (node (ref "U$2") (pin "P$12") (pinfunction "AGND_P$12") (pintype "bidirectional"))
      (node (ref "U$2") (pin "P$3") (pinfunction "PGND1_P$3") (pintype "bidirectional"))
      (node (ref "U$2") (pin "P$4") (pinfunction "PGND2_P$4") (pintype "bidirectional"))
      (node (ref "U$2") (pin "P$5") (pinfunction "PGND3_P$5") (pintype "bidirectional"))
      (node (ref "U$2") (pin "P$8") (pinfunction "PGND4_P$8") (pintype "bidirectional"))
      (node (ref "U$2") (pin "P$9") (pinfunction "PGND5_P$9") (pintype "bidirectional"))
      (node (ref "U$22") (pin "P$2") (pinfunction "P$2_P$2") (pintype "bidirectional"))
      (node (ref "U$4") (pin "1") (pinfunction "VSS_1") (pintype "bidirectional"))
      (node (ref "U$6") (pin "P$2") (pinfunction "P$2_P$2") (pintype "bidirectional"))
      (node (ref "U$7") (pin "P$2") (pinfunction "GND_P$2") (pintype "bidirectional"))
      (node (ref "X1") (pin "1") (pinfunction "S_1") (pintype "passive"))
    )
    (net (code "34") (name "Net-(C6-Pad1)") (class "Default")
      (node (ref "C6") (pin "1") (pinfunction "1_1") (pintype "passive"))
      (node (ref "U$1") (pin "P$14") (pinfunction "P$14_P$14") (pintype "bidirectional"))
      (node (ref "U$1") (pin "P$15") (pinfunction "P$15_P$15") (pintype "bidirectional"))
    )
    (net (code "35") (name "Net-(C12-Pad2)") (class "Default")
      (node (ref "C12") (pin "2") (pinfunction "2_2") (pintype "passive"))
      (node (ref "C13") (pin "1") (pinfunction "1_1") (pintype "passive"))
      (node (ref "U$1") (pin "P$30") (pinfunction "P$30_P$30") (pintype "bidirectional"))
    )
    (net (code "36") (name "Net-(C13-Pad2)") (class "Default")
      (node (ref "C13") (pin "2") (pinfunction "2_2") (pintype "passive"))
      (node (ref "C14") (pin "1") (pinfunction "1_1") (pintype "passive"))
      (node (ref "U$1") (pin "P$31") (pinfunction "P$31_P$31") (pintype "bidirectional"))
    )
    (net (code "37") (name "Net-(C14-Pad2)") (class "Default")
      (node (ref "C14") (pin "2") (pinfunction "2_2") (pintype "passive"))
      (node (ref "C15") (pin "1") (pinfunction "1_1") (pintype "passive"))
      (node (ref "U$1") (pin "P$32") (pinfunction "P$32_P$32") (pintype "bidirectional"))
    )
    (net (code "38") (name "Net-(L$2-1)") (class "Default")
      (node (ref "C36") (pin "2") (pinfunction "2_2") (pintype "passive"))
      (node (ref "L$2") (pin "P$1") (pinfunction "1_P$1") (pintype "passive"))
      (node (ref "U$7") (pin "P$6") (pinfunction "LX_P$6") (pintype "bidirectional"))
    )
    (net (code "39") (name "Net-(R12-Pad2)") (class "Default")
      (node (ref "R12") (pin "2") (pinfunction "2_2") (pintype "passive"))
      (node (ref "R35") (pin "1") (pinfunction "1_1") (pintype "passive"))
    )
    (net (code "40") (name "Net-(R17-Pad1)") (class "Default")
      (node (ref "R17") (pin "1") (pinfunction "1_1") (pintype "passive"))
      (node (ref "R18") (pin "2") (pinfunction "2_2") (pintype "passive"))
    )
    (net (code "41") (name "Net-(T1-B)") (class "Default")
      (node (ref "R6") (pin "1") (pinfunction "1_1") (pintype "passive"))
      (node (ref "T1") (pin "1") (pinfunction "B_1") (pintype "passive"))
    )
    (net (code "42") (name "Net-(T2-B)") (class "Default")
      (node (ref "R10") (pin "1") (pinfunction "1_1") (pintype "passive"))
      (node (ref "T2") (pin "1") (pinfunction "B_1") (pintype "passive"))
    )
    (net (code "43") (name "Net-(T2-C)") (class "Default")
      (node (ref "JP1") (pin "1") (pinfunction "1_1") (pintype "passive"))
      (node (ref "T2") (pin "3") (pinfunction "C_3") (pintype "passive"))
    )
    (net (code "44") (name "Net-(U$2-BOOT)") (class "Default")
      (node (ref "C24") (pin "2") (pinfunction "2_2") (pintype "passive"))
      (node (ref "U$2") (pin "P$1") (pinfunction "BOOT_P$1") (pintype "bidirectional"))
    )
    (net (code "45") (name "Net-(U$2-MODE)") (class "Default")
      (node (ref "R1") (pin "1") (pinfunction "1_1") (pintype "passive"))
      (node (ref "R9") (pin "2") (pinfunction "2_2") (pintype "passive"))
      (node (ref "U$2") (pin "P$18") (pinfunction "MODE_P$18") (pintype "bidirectional"))
    )
    (net (code "46") (name "Net-(U$2-SW1)") (class "Default")
      (node (ref "C24") (pin "1") (pinfunction "1_1") (pintype "passive"))
      (node (ref "U$2") (pin "P$6") (pinfunction "SW1_P$6") (pintype "bidirectional"))
      (node (ref "U$2") (pin "P$7") (pinfunction "SW2_P$7") (pintype "bidirectional"))
      (node (ref "U$3") (pin "P$1") (pinfunction "1_P$1") (pintype "passive"))
    )
    (net (code "47") (name "Net-(U$2-VREG5)") (class "Default")
      (node (ref "C4") (pin "1") (pinfunction "1_1") (pintype "passive"))
      (node (ref "R9") (pin "1") (pinfunction "1_1") (pintype "passive"))
      (node (ref "U$2") (pin "P$17") (pinfunction "VREG5_P$17") (pintype "bidirectional"))
    )
    (net (code "48") (name "Net-(U$7-BS)") (class "Default")
      (node (ref "C36") (pin "1") (pinfunction "1_1") (pintype "passive"))
      (node (ref "U$7") (pin "P$1") (pinfunction "BS_P$1") (pintype "bidirectional"))
    )
    (net (code "49") (name "Net-(U$7-FB)") (class "Default")
      (node (ref "R40") (pin "1") (pinfunction "1_1") (pintype "passive"))
      (node (ref "R41") (pin "2") (pinfunction "2_2") (pintype "passive"))
      (node (ref "U$7") (pin "P$3") (pinfunction "FB_P$3") (pintype "bidirectional"))
    )
    (net (code "50") (name "Net-(U$14-P$5)") (class "Default")
      (node (ref "C7") (pin "2") (pinfunction "2_2") (pintype "passive"))
      (node (ref "L4") (pin "2") (pinfunction "2_2") (pintype "passive"))
      (node (ref "U$14") (pin "5") (pinfunction "P$5_5") (pintype "power_in"))
    )
    (net (code "51") (name "Net-(U$16-P$2A5)") (class "Default")
      (node (ref "R22") (pin "1") (pinfunction "1_1") (pintype "passive"))
      (node (ref "U$16") (pin "P$203A5") (pinfunction "P$2A5_P$203A5") (pintype "bidirectional"))
    )
    (net (code "52") (name "Net-(U$16-P$3B5)") (class "Default")
      (node (ref "R16") (pin "1") (pinfunction "1_1") (pintype "passive"))
      (node (ref "U$16") (pin "P$210B5") (pinfunction "P$3B5_P$210B5") (pintype "bidirectional"))
    )
    (net (code "53") (name "unconnected-(D1-PadDO)") (class "Default")
      (node (ref "D1") (pin "DO") (pinfunction "DO_DO") (pintype "bidirectional"))
    )
    (net (code "54") (name "unconnected-(ESP32C3-MINI-1-PadP$4)") (class "Default")
      (node (ref "ESP32C3-MINI-1") (pin "P$4") (pinfunction "P$4_P$4") (pintype "bidirectional"))
    )
    (net (code "55") (name "unconnected-(ESP32C3-MINI-1-PadP$7)") (class "Default")
      (node (ref "ESP32C3-MINI-1") (pin "P$7") (pinfunction "P$7_P$7") (pintype "bidirectional"))
    )
    (net (code "56") (name "unconnected-(ESP32C3-MINI-1-PadP$9)") (class "Default")
      (node (ref "ESP32C3-MINI-1") (pin "P$9") (pinfunction "P$9_P$9") (pintype "bidirectional"))
    )
    (net (code "57") (name "unconnected-(ESP32C3-MINI-1-PadP$10)") (class "Default")
      (node (ref "ESP32C3-MINI-1") (pin "P$10") (pinfunction "P$10_P$10") (pintype "bidirectional"))
    )
    (net (code "58") (name "unconnected-(ESP32C3-MINI-1-PadP$12)") (class "Default")
      (node (ref "ESP32C3-MINI-1") (pin "P$12") (pinfunction "P$12_P$12") (pintype "bidirectional"))
    )
    (net (code "59") (name "unconnected-(ESP32C3-MINI-1-PadP$14)") (class "Default")
      (node (ref "ESP32C3-MINI-1") (pin "P$14") (pinfunction "P$14_P$14") (pintype "bidirectional"))
    )
    (net (code "60") (name "unconnected-(ESP32C3-MINI-1-PadP$15)") (class "Default")
      (node (ref "ESP32C3-MINI-1") (pin "P$15") (pinfunction "P$15_P$15") (pintype "bidirectional"))
    )
    (net (code "61") (name "unconnected-(ESP32C3-MINI-1-PadP$17)") (class "Default")
      (node (ref "ESP32C3-MINI-1") (pin "P$17") (pinfunction "P$17_P$17") (pintype "bidirectional"))
    )
    (net (code "62") (name "unconnected-(ESP32C3-MINI-1-PadP$24)") (class "Default")
      (node (ref "ESP32C3-MINI-1") (pin "P$24") (pinfunction "P$24_P$24") (pintype "bidirectional"))
    )
    (net (code "63") (name "unconnected-(ESP32C3-MINI-1-PadP$25)") (class "Default")
      (node (ref "ESP32C3-MINI-1") (pin "P$25") (pinfunction "P$25_P$25") (pintype "bidirectional"))
    )
    (net (code "64") (name "unconnected-(ESP32C3-MINI-1-PadP$28)") (class "Default")
      (node (ref "ESP32C3-MINI-1") (pin "P$28") (pinfunction "P$28_P$28") (pintype "bidirectional"))
    )
    (net (code "65") (name "unconnected-(ESP32C3-MINI-1-PadP$29)") (class "Default")
      (node (ref "ESP32C3-MINI-1") (pin "P$29") (pinfunction "P$29_P$29") (pintype "bidirectional"))
    )
    (net (code "66") (name "unconnected-(ESP32C3-MINI-1-PadP$32)") (class "Default")
      (node (ref "ESP32C3-MINI-1") (pin "P$32") (pinfunction "P$32_P$32") (pintype "bidirectional"))
    )
    (net (code "67") (name "unconnected-(ESP32C3-MINI-1-PadP$33)") (class "Default")
      (node (ref "ESP32C3-MINI-1") (pin "P$33") (pinfunction "P$33_P$33") (pintype "bidirectional"))
    )
    (net (code "68") (name "unconnected-(ESP32C3-MINI-1-PadP$34)") (class "Default")
      (node (ref "ESP32C3-MINI-1") (pin "P$34") (pinfunction "P$34_P$34") (pintype "bidirectional"))
    )
    (net (code "69") (name "unconnected-(ESP32C3-MINI-1-PadP$35)") (class "Default")
      (node (ref "ESP32C3-MINI-1") (pin "P$35") (pinfunction "P$35_P$35") (pintype "bidirectional"))
    )
    (net (code "70") (name "unconnected-(JP1-Pad2)") (class "Default")
      (node (ref "JP1") (pin "2") (pinfunction "2_2") (pintype "passive"))
    )
    (net (code "71") (name "unconnected-(U$1-PadP$1)") (class "Default")
      (node (ref "U$1") (pin "P$1") (pinfunction "P$1_P$1") (pintype "bidirectional"))
    )
    (net (code "72") (name "unconnected-(U$1-PadP$2)") (class "Default")
      (node (ref "U$1") (pin "P$2") (pinfunction "P$2_P$2") (pintype "bidirectional"))
    )
    (net (code "73") (name "unconnected-(U$1-PadP$3)") (class "Default")
      (node (ref "U$1") (pin "P$3") (pinfunction "P$3_P$3") (pintype "bidirectional"))
    )
    (net (code "74") (name "unconnected-(U$1-PadP$7)") (class "Default")
      (node (ref "U$1") (pin "P$7") (pinfunction "P$7_P$7") (pintype "bidirectional"))
    )
    (net (code "75") (name "unconnected-(U$1-PadP$20)") (class "Default")
      (node (ref "U$1") (pin "P$20") (pinfunction "P$20_P$20") (pintype "bidirectional"))
    )
    (net (code "76") (name "unconnected-(U$1-PadP$22)") (class "Default")
      (node (ref "U$1") (pin "P$22") (pinfunction "P$22_P$22") (pintype "bidirectional"))
    )
    (net (code "77") (name "unconnected-(U$1-PadP$23)") (class "Default")
      (node (ref "U$1") (pin "P$23") (pinfunction "P$23_P$23") (pintype "bidirectional"))
    )
    (net (code "78") (name "unconnected-(U$1-PadP$24)") (class "Default")
      (node (ref "U$1") (pin "P$24") (pinfunction "P$24_P$24") (pintype "bidirectional"))
    )
    (net (code "79") (name "unconnected-(U$1-PadP$26)") (class "Default")
      (node (ref "U$1") (pin "P$26") (pinfunction "P$26_P$26") (pintype "bidirectional"))
    )
    (net (code "80") (name "unconnected-(U$1-PadP$28)") (class "Default")
      (node (ref "U$1") (pin "P$28") (pinfunction "P$28_P$28") (pintype "bidirectional"))
    )
    (net (code "81") (name "unconnected-(U$1-PadP$29)") (class "Default")
      (node (ref "U$1") (pin "P$29") (pinfunction "P$29_P$29") (pintype "bidirectional"))
    )
    (net (code "82") (name "unconnected-(U$2-PGOOD-PadP$16)") (class "Default")
      (node (ref "U$2") (pin "P$16") (pinfunction "PGOOD_P$16") (pintype "bidirectional"))
    )
    (net (code "83") (name "unconnected-(U$2-SS-PadP$14)") (class "Default")
      (node (ref "U$2") (pin "P$14") (pinfunction "SS_P$14") (pintype "bidirectional"))
    )
    (net (code "84") (name "unconnected-(U$14-P$6-Pad6)") (class "Default")
      (node (ref "U$14") (pin "6") (pinfunction "P$6_6") (pintype "bidirectional"))
    )
    (net (code "85") (name "unconnected-(U$14-P$7-Pad7)") (class "Default")
      (node (ref "U$14") (pin "7") (pinfunction "P$7_7") (pintype "no_connect"))
    )
    (net (code "86") (name "unconnected-(U$16-P$8A8-PadP$209A8)") (class "Default")
      (node (ref "U$16") (pin "P$209A8") (pinfunction "P$8A8_P$209A8") (pintype "bidirectional"))
    )
    (net (code "87") (name "unconnected-(U$16-P$9B8-PadP$202B8)") (class "Default")
      (node (ref "U$16") (pin "P$202B8") (pinfunction "P$9B8_P$202B8") (pintype "bidirectional"))
    )
  )
)
